# Sheet.net
KiCad netlist of a schematic drawn in Altium Designer
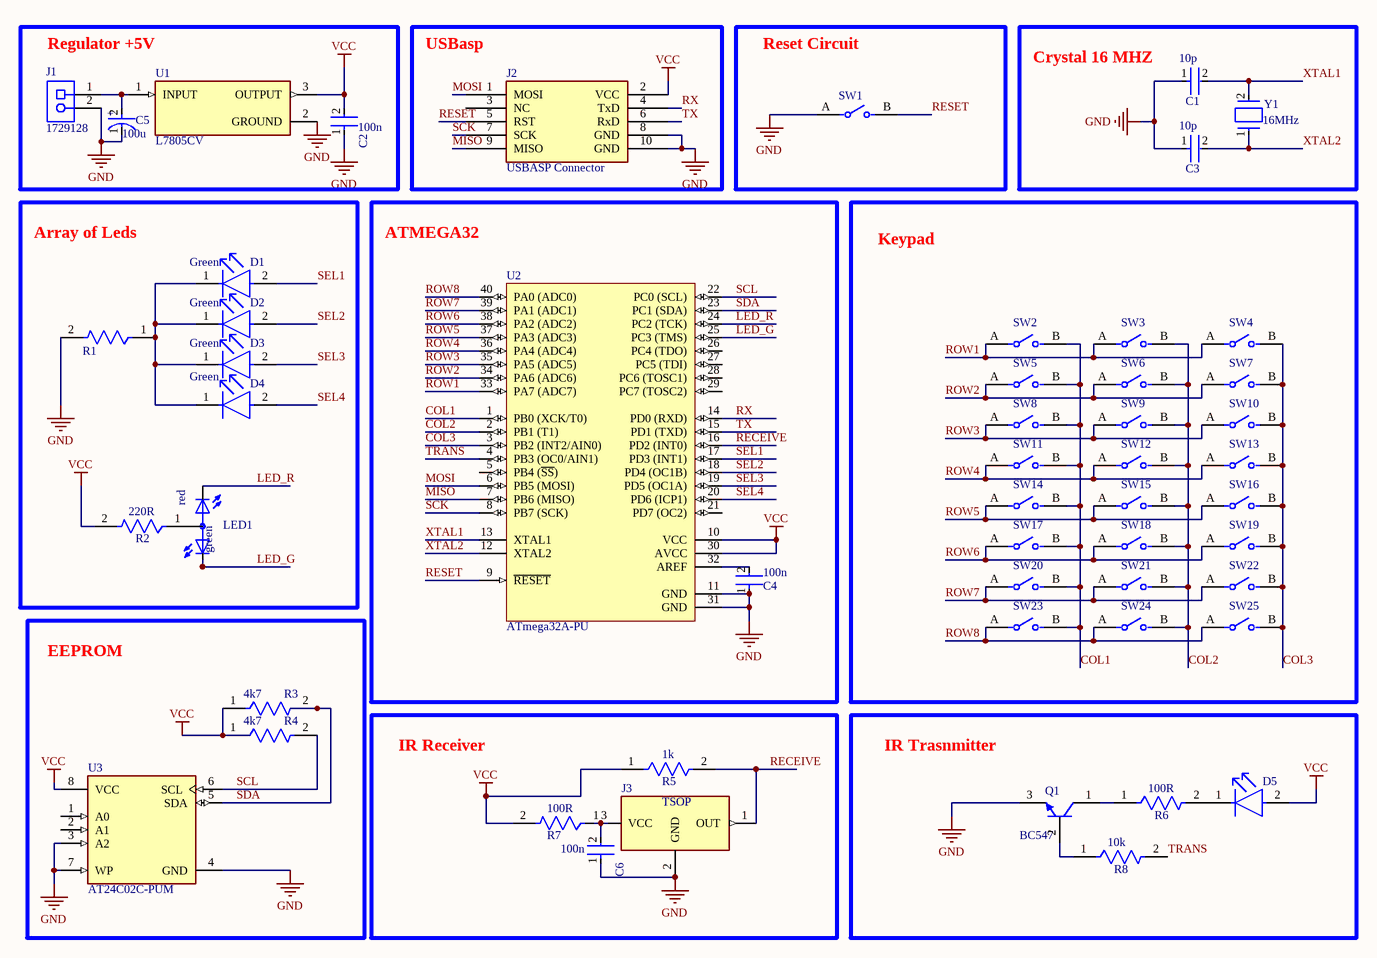
[diagram p0: Sheet.SchDoc]

(export (version "E")
  (design (tool "Eeschema 10.0.6"))
  (components
    (comp (ref "C1")
      (value "10p")
      (footprint "FP-K155L2-MFG")
      (description "K103K15X7RF5TL2 Multilayer Ceramic Capacitor, 0.01 uF, 50 V, ± 10%, X7R, Radial Leaded")
      (fields
        (field (name "VOLTAGE") "50V")
        (field (name "CAPACITANCE") "10p")
        (field (name "TOLERANCE") "10%")
      )
      (libsource (lib "Altium Content Vault") (part "02cd4be3c70576c341d710602a673aa"))
    )
    (comp (ref "C2")
      (value "K103K15X7RF5TL2")
      (footprint "FP-K155L2-MFG")
      (description "K103K15X7RF5TL2 Multilayer Ceramic Capacitor, 0.01 uF, 50 V, ± 10%, X7R, Radial Leaded")
      (fields
        (field (name "VOLTAGE") "50V")
        (field (name "CAPACITANCE") "100n")
        (field (name "TOLERANCE") "10%")
      )
      (libsource (lib "Altium Content Vault") (part "02cd4be3c70576c341d710602a673aa"))
    )
    (comp (ref "C3")
      (value "10p")
      (footprint "FP-K155L2-MFG")
      (description "K103K15X7RF5TL2 Multilayer Ceramic Capacitor, 0.01 uF, 50 V, ± 10%, X7R, Radial Leaded")
      (fields
        (field (name "VOLTAGE") "50V")
        (field (name "CAPACITANCE") "10p")
        (field (name "TOLERANCE") "10%")
      )
      (libsource (lib "Altium Content Vault") (part "02cd4be3c70576c341d710602a673aa"))
    )
    (comp (ref "C4")
      (value "100n")
      (footprint "FP-K155L2-MFG")
      (description "K103K15X7RF5TL2 Multilayer Ceramic Capacitor, 0.01 uF, 50 V, ± 10%, X7R, Radial Leaded")
      (fields (field (name "VOLTAGE") "50V") (field (name "TOLERANCE") "10%"))
      (libsource (lib "Altium Content Vault") (part "02cd4be3c70576c341d710602a673aa"))
    )
    (comp (ref "C5")
      (value "EEUHD1E101")
      (footprint "FP-RAD-TH-D_6_3_0_5-L_11-MFG")
      (description "Aluminum Electrolytic Capacitors (Radial Lead Type) AEC-Q200 Qualified 100uF ±20% 25V")
      (fields
        (field (name "TOLERANCE") "20%")
        (field (name "CAPACITANCE") "100u")
        (field (name "VOLTAGE") "25V")
      )
      (libsource (lib "Altium Content Vault") (part "a00bbbee19879c290e62620ae7e47b1"))
    )
    (comp (ref "C6")
      (value "K103K15X7RF5TL2")
      (footprint "FP-K155L2-MFG")
      (description "K103K15X7RF5TL2 Multilayer Ceramic Capacitor, 0.01 uF, 50 V, ± 10%, X7R, Radial Leaded")
      (fields
        (field (name "VOLTAGE") "50V")
        (field (name "CAPACITANCE") "100n")
        (field (name "TOLERANCE") "10%")
      )
      (libsource (lib "Altium Content Vault") (part "02cd4be3c70576c341d710602a673aa"))
    )
    (comp (ref "D1")
      (value "TLLG4401")
      (footprint "FP-6_544-5255_01-4-MFG")
      (description "TLLG4401 LED, Green, 2mcd, 3mmDia., T-1, +/-25deg, 565nm, 7mA, 1.9V Vf, 20V Vr, 20mW, -40")
      (fields (field (name "COLOR") "Green"))
      (libsource (lib "Altium Content Vault") (part "8706943c75ba83719d021d2fdc84c58"))
    )
    (comp (ref "D2")
      (value "TLLG4401")
      (footprint "FP-6_544-5255_01-4-MFG")
      (description "TLLG4401 LED, Green, 2mcd, 3mmDia., T-1, +/-25deg, 565nm, 7mA, 1.9V Vf, 20V Vr, 20mW, -40")
      (fields (field (name "COLOR") "Green"))
      (libsource (lib "Altium Content Vault") (part "8706943c75ba83719d021d2fdc84c58"))
    )
    (comp (ref "D3")
      (value "TLLG4401")
      (footprint "FP-6_544-5255_01-4-MFG")
      (description "TLLG4401 LED, Green, 2mcd, 3mmDia., T-1, +/-25deg, 565nm, 7mA, 1.9V Vf, 20V Vr, 20mW, -40")
      (fields (field (name "COLOR") "Green"))
      (libsource (lib "Altium Content Vault") (part "8706943c75ba83719d021d2fdc84c58"))
    )
    (comp (ref "D4")
      (value "TLLG4401")
      (footprint "FP-6_544-5255_01-4-MFG")
      (description "TLLG4401 LED, Green, 2mcd, 3mmDia., T-1, +/-25deg, 565nm, 7mA, 1.9V Vf, 20V Vr, 20mW, -40")
      (fields (field (name "COLOR") "Green"))
      (libsource (lib "Altium Content Vault") (part "8706943c75ba83719d021d2fdc84c58"))
    )
    (comp (ref "D5")
      (value "TLLG4401")
      (footprint "FP-6_544-5255_01-4-MFG")
      (description "TLLG4401 LED, Green, 2mcd, 3mmDia., T-1, +/-25deg, 565nm, 7mA, 1.9V Vf, 20V Vr, 20mW, -40")
      (libsource (lib "Altium Content Vault") (part "8706943c75ba83719d021d2fdc84c58"))
    )
    (comp (ref "J1")
      (value "1729128")
      (footprint "PHOE-1729128-2_V")
      (description "PCB Terminal Block, 13.5 A, 400 V, 2-Pin THD, RoHS, Bulk")
      (fields (field (name "MANUFACTURER") "Phoenix Contact"))
      (libsource (lib "Altium Content Vault") (part "CN-2P-F-R2"))
    )
    (comp (ref "J2")
      (value "USBASP Connector")
      (footprint "SamacSys:SHDR10W99P254_2X5_2032X889X927P")
      (description "Connector")
      (fields
        (field (name "MANUFACTURER_PART_NUMBER") "70246-1001")
        (field (name "MOUSER PART NUMBER") "538-70246-1001")
      )
      (libsource (lib "YoussifLIB") (part "USBASP Connector"))
    )
    (comp (ref "J3")
      (value "TSOP1838")
      (footprint "TSOP1838")
      (description "IR Remote Receiver 38KHz 35m 3-Pin")
      (fields (field (name "MF") "Vishay"))
      (libsource (lib "IR_Receiver") (part "TSOP1838"))
    )
    (comp (ref "LED1")
      (value "L-59EGW-CA")
      (footprint "L-59EGW-CA")
      (description "LED; 5mm; bicolour; red/green; 5mcd; 5mcd; 60Â°; Front: convex; anode")
      (fields (field (name "MF") "Kingbright"))
      (libsource (lib "YoussifLIB") (part "L-59EGW-CA"))
    )
    (comp (ref "Q1")
      (value "BC547")
      (footprint "ONSC-TO-92-3-29-11_AM_BL")
      (description "Amplifier Transistor, NPN Silicon, 3-Pin TO-92, Pb-Free, Ammo Box")
      (fields (field (name "MANUFACTURER") "On Semiconductor") (field (name "PARTNUMBER") "BC547BZL1G"))
      (libsource (lib "Altium Content Vault") (part "ONSC-NPN-C1B2E3-3"))
    )
    (comp (ref "R1")
      (value "MRS25000C1001FCT00")
      (footprint "FP-MRS25-MFG")
      (description "RES 1K OHM 0.6W 1% AXIAL")
      (fields (field (name "TOLERANCE") "1%"))
      (libsource (lib "Altium Content Vault") (part "1029c3af85768c4190bb7ad29bc67b5"))
    )
    (comp (ref "R2")
      (value "220R")
      (footprint "FP-MRS25-MFG")
      (description "RES 1K OHM 0.6W 1% AXIAL")
      (fields (field (name "TOLERANCE") "1%") (field (name "RESISTANCE") "220R"))
      (libsource (lib "Altium Content Vault") (part "1029c3af85768c4190bb7ad29bc67b5"))
    )
    (comp (ref "R3")
      (value "4k7")
      (footprint "FP-MRS25-MFG")
      (description "RES 1K OHM 0.6W 1% AXIAL")
      (fields (field (name "TOLERANCE") "1%") (field (name "RESISTANCE") "4k7"))
      (libsource (lib "Altium Content Vault") (part "1029c3af85768c4190bb7ad29bc67b5"))
    )
    (comp (ref "R4")
      (value "4k7")
      (footprint "FP-MRS25-MFG")
      (description "RES 1K OHM 0.6W 1% AXIAL")
      (fields (field (name "TOLERANCE") "1%") (field (name "RESISTANCE") "4k7"))
      (libsource (lib "Altium Content Vault") (part "1029c3af85768c4190bb7ad29bc67b5"))
    )
    (comp (ref "R5")
      (value "1k")
      (footprint "FP-MRS25-MFG")
      (description "RES 1K OHM 0.6W 1% AXIAL")
      (fields (field (name "TOLERANCE") "1%") (field (name "RESISTANCE") "1k"))
      (libsource (lib "Altium Content Vault") (part "1029c3af85768c4190bb7ad29bc67b5"))
    )
    (comp (ref "R6")
      (value "100R")
      (footprint "FP-MRS25-MFG")
      (description "RES 1K OHM 0.6W 1% AXIAL")
      (fields (field (name "TOLERANCE") "1%") (field (name "RESISTANCE") "100R"))
      (libsource (lib "Altium Content Vault") (part "1029c3af85768c4190bb7ad29bc67b5"))
    )
    (comp (ref "R7")
      (value "100R")
      (footprint "FP-MRS25-MFG")
      (description "RES 1K OHM 0.6W 1% AXIAL")
      (fields (field (name "TOLERANCE") "1%") (field (name "RESISTANCE") "100R"))
      (libsource (lib "Altium Content Vault") (part "1029c3af85768c4190bb7ad29bc67b5"))
    )
    (comp (ref "R8")
      (value "10k")
      (footprint "FP-MRS25-MFG")
      (description "RES 1K OHM 0.6W 1% AXIAL")
      (fields (field (name "TOLERANCE") "1%") (field (name "RESISTANCE") "10k"))
      (libsource (lib "Altium Content Vault") (part "1029c3af85768c4190bb7ad29bc67b5"))
    )
    (comp (ref "SW1")
      (value "EVQ-21505R")
      (footprint "FP-EVQ-21505R-MFG")
      (description "SWITCH TACTILE SPST-NO 0.02A 15V")
      (libsource (lib "Altium Content Vault") (part "2b0b2b19372efd94fa7681498149756"))
    )
    (comp (ref "SW2")
      (value "EVQ-21505R")
      (footprint "FP-EVQ-21505R-MFG")
      (description "SWITCH TACTILE SPST-NO 0.02A 15V")
      (libsource (lib "Altium Content Vault") (part "2b0b2b19372efd94fa7681498149756"))
    )
    (comp (ref "SW3")
      (value "EVQ-21505R")
      (footprint "FP-EVQ-21505R-MFG")
      (description "SWITCH TACTILE SPST-NO 0.02A 15V")
      (libsource (lib "Altium Content Vault") (part "2b0b2b19372efd94fa7681498149756"))
    )
    (comp (ref "SW4")
      (value "EVQ-21505R")
      (footprint "FP-EVQ-21505R-MFG")
      (description "SWITCH TACTILE SPST-NO 0.02A 15V")
      (libsource (lib "Altium Content Vault") (part "2b0b2b19372efd94fa7681498149756"))
    )
    (comp (ref "SW5")
      (value "EVQ-21505R")
      (footprint "FP-EVQ-21505R-MFG")
      (description "SWITCH TACTILE SPST-NO 0.02A 15V")
      (libsource (lib "Altium Content Vault") (part "2b0b2b19372efd94fa7681498149756"))
    )
    (comp (ref "SW6")
      (value "EVQ-21505R")
      (footprint "FP-EVQ-21505R-MFG")
      (description "SWITCH TACTILE SPST-NO 0.02A 15V")
      (libsource (lib "Altium Content Vault") (part "2b0b2b19372efd94fa7681498149756"))
    )
    (comp (ref "SW7")
      (value "EVQ-21505R")
      (footprint "FP-EVQ-21505R-MFG")
      (description "SWITCH TACTILE SPST-NO 0.02A 15V")
      (libsource (lib "Altium Content Vault") (part "2b0b2b19372efd94fa7681498149756"))
    )
    (comp (ref "SW8")
      (value "EVQ-21505R")
      (footprint "FP-EVQ-21505R-MFG")
      (description "SWITCH TACTILE SPST-NO 0.02A 15V")
      (libsource (lib "Altium Content Vault") (part "2b0b2b19372efd94fa7681498149756"))
    )
    (comp (ref "SW9")
      (value "EVQ-21505R")
      (footprint "FP-EVQ-21505R-MFG")
      (description "SWITCH TACTILE SPST-NO 0.02A 15V")
      (libsource (lib "Altium Content Vault") (part "2b0b2b19372efd94fa7681498149756"))
    )
    (comp (ref "SW10")
      (value "EVQ-21505R")
      (footprint "FP-EVQ-21505R-MFG")
      (description "SWITCH TACTILE SPST-NO 0.02A 15V")
      (libsource (lib "Altium Content Vault") (part "2b0b2b19372efd94fa7681498149756"))
    )
    (comp (ref "SW11")
      (value "EVQ-21505R")
      (footprint "FP-EVQ-21505R-MFG")
      (description "SWITCH TACTILE SPST-NO 0.02A 15V")
      (libsource (lib "Altium Content Vault") (part "2b0b2b19372efd94fa7681498149756"))
    )
    (comp (ref "SW12")
      (value "EVQ-21505R")
      (footprint "FP-EVQ-21505R-MFG")
      (description "SWITCH TACTILE SPST-NO 0.02A 15V")
      (libsource (lib "Altium Content Vault") (part "2b0b2b19372efd94fa7681498149756"))
    )
    (comp (ref "SW13")
      (value "EVQ-21505R")
      (footprint "FP-EVQ-21505R-MFG")
      (description "SWITCH TACTILE SPST-NO 0.02A 15V")
      (libsource (lib "Altium Content Vault") (part "2b0b2b19372efd94fa7681498149756"))
    )
    (comp (ref "SW14")
      (value "EVQ-21505R")
      (footprint "FP-EVQ-21505R-MFG")
      (description "SWITCH TACTILE SPST-NO 0.02A 15V")
      (libsource (lib "Altium Content Vault") (part "2b0b2b19372efd94fa7681498149756"))
    )
    (comp (ref "SW15")
      (value "EVQ-21505R")
      (footprint "FP-EVQ-21505R-MFG")
      (description "SWITCH TACTILE SPST-NO 0.02A 15V")
      (libsource (lib "Altium Content Vault") (part "2b0b2b19372efd94fa7681498149756"))
    )
    (comp (ref "SW16")
      (value "EVQ-21505R")
      (footprint "FP-EVQ-21505R-MFG")
      (description "SWITCH TACTILE SPST-NO 0.02A 15V")
      (libsource (lib "Altium Content Vault") (part "2b0b2b19372efd94fa7681498149756"))
    )
    (comp (ref "SW17")
      (value "EVQ-21505R")
      (footprint "FP-EVQ-21505R-MFG")
      (description "SWITCH TACTILE SPST-NO 0.02A 15V")
      (libsource (lib "Altium Content Vault") (part "2b0b2b19372efd94fa7681498149756"))
    )
    (comp (ref "SW18")
      (value "EVQ-21505R")
      (footprint "FP-EVQ-21505R-MFG")
      (description "SWITCH TACTILE SPST-NO 0.02A 15V")
      (libsource (lib "Altium Content Vault") (part "2b0b2b19372efd94fa7681498149756"))
    )
    (comp (ref "SW19")
      (value "EVQ-21505R")
      (footprint "FP-EVQ-21505R-MFG")
      (description "SWITCH TACTILE SPST-NO 0.02A 15V")
      (libsource (lib "Altium Content Vault") (part "2b0b2b19372efd94fa7681498149756"))
    )
    (comp (ref "SW20")
      (value "EVQ-21505R")
      (footprint "FP-EVQ-21505R-MFG")
      (description "SWITCH TACTILE SPST-NO 0.02A 15V")
      (libsource (lib "Altium Content Vault") (part "2b0b2b19372efd94fa7681498149756"))
    )
    (comp (ref "SW21")
      (value "EVQ-21505R")
      (footprint "FP-EVQ-21505R-MFG")
      (description "SWITCH TACTILE SPST-NO 0.02A 15V")
      (libsource (lib "Altium Content Vault") (part "2b0b2b19372efd94fa7681498149756"))
    )
    (comp (ref "SW22")
      (value "EVQ-21505R")
      (footprint "FP-EVQ-21505R-MFG")
      (description "SWITCH TACTILE SPST-NO 0.02A 15V")
      (libsource (lib "Altium Content Vault") (part "2b0b2b19372efd94fa7681498149756"))
    )
    (comp (ref "SW23")
      (value "EVQ-21505R")
      (footprint "FP-EVQ-21505R-MFG")
      (description "SWITCH TACTILE SPST-NO 0.02A 15V")
      (libsource (lib "Altium Content Vault") (part "2b0b2b19372efd94fa7681498149756"))
    )
    (comp (ref "SW24")
      (value "EVQ-21505R")
      (footprint "FP-EVQ-21505R-MFG")
      (description "SWITCH TACTILE SPST-NO 0.02A 15V")
      (libsource (lib "Altium Content Vault") (part "2b0b2b19372efd94fa7681498149756"))
    )
    (comp (ref "SW25")
      (value "EVQ-21505R")
      (footprint "FP-EVQ-21505R-MFG")
      (description "SWITCH TACTILE SPST-NO 0.02A 15V")
      (libsource (lib "Altium Content Vault") (part "2b0b2b19372efd94fa7681498149756"))
    )
    (comp (ref "U1")
      (value "L7805CV")
      (footprint "TO255P1040X460X1968-3")
      (description "Linear Voltage Regulator IC Positive Fixed 1 Output 1.5A TO-220")
      (fields (field (name "MF") "STMicroelectronics"))
      (libsource (lib "L7805CV") (part "L7805CV"))
    )
    (comp (ref "U2")
      (value "ATmega32A-PU")
      (footprint "40P6")
      (libsource (lib "Altium Content Vault") (part "MC-8B-AT16A-IL40"))
    )
    (comp (ref "U3")
      (value "AT24C02C-PUM")
      (footprint "FP-C04-018-P-MFG")
      (description "AT24C02C-PUM EEPROM Serial-2Wire 2K-bit 256 x 8 1.8V/2.5V/3.3V/5V 8-Pin PDIP W Bulk - Rail/Tube")
      (libsource (lib "Altium Content Vault") (part "089d7b6fce1835f83e6218732eee8eb"))
    )
    (comp (ref "Y1")
      (value "16MHz")
      (footprint "FP-ECS-80-20-4X-MFG")
      (fields (field (name "FREQUENCY") "16MHz") (field (name "TOLERANCE") "0.003%"))
      (libsource (lib "Altium Content Vault") (part "c23a69dc6c9e2f18f2079038eb95dd1"))
    )
  )
  (nets
    (net (code "1") (name "/COL1") (class "Default")
      (node (ref "SW11") (pin "B") (pinfunction "B_B") (pintype "passive"))
      (node (ref "SW14") (pin "B") (pinfunction "B_B") (pintype "passive"))
      (node (ref "SW17") (pin "B") (pinfunction "B_B") (pintype "passive"))
      (node (ref "SW2") (pin "B") (pinfunction "B_B") (pintype "passive"))
      (node (ref "SW20") (pin "B") (pinfunction "B_B") (pintype "passive"))
      (node (ref "SW23") (pin "B") (pinfunction "B_B") (pintype "passive"))
      (node (ref "SW5") (pin "B") (pinfunction "B_B") (pintype "passive"))
      (node (ref "SW8") (pin "B") (pinfunction "B_B") (pintype "passive"))
      (node (ref "U2") (pin "1") (pinfunction "PB0_(XCK/T0)_1") (pintype "bidirectional"))
    )
    (net (code "2") (name "/COL2") (class "Default")
      (node (ref "SW12") (pin "B") (pinfunction "B_B") (pintype "passive"))
      (node (ref "SW15") (pin "B") (pinfunction "B_B") (pintype "passive"))
      (node (ref "SW18") (pin "B") (pinfunction "B_B") (pintype "passive"))
      (node (ref "SW21") (pin "B") (pinfunction "B_B") (pintype "passive"))
      (node (ref "SW24") (pin "B") (pinfunction "B_B") (pintype "passive"))
      (node (ref "SW3") (pin "B") (pinfunction "B_B") (pintype "passive"))
      (node (ref "SW6") (pin "B") (pinfunction "B_B") (pintype "passive"))
      (node (ref "SW9") (pin "B") (pinfunction "B_B") (pintype "passive"))
      (node (ref "U2") (pin "2") (pinfunction "PB1_(T1)_2") (pintype "bidirectional"))
    )
    (net (code "3") (name "/COL3") (class "Default")
      (node (ref "SW10") (pin "B") (pinfunction "B_B") (pintype "passive"))
      (node (ref "SW13") (pin "B") (pinfunction "B_B") (pintype "passive"))
      (node (ref "SW16") (pin "B") (pinfunction "B_B") (pintype "passive"))
      (node (ref "SW19") (pin "B") (pinfunction "B_B") (pintype "passive"))
      (node (ref "SW22") (pin "B") (pinfunction "B_B") (pintype "passive"))
      (node (ref "SW25") (pin "B") (pinfunction "B_B") (pintype "passive"))
      (node (ref "SW4") (pin "B") (pinfunction "B_B") (pintype "passive"))
      (node (ref "SW7") (pin "B") (pinfunction "B_B") (pintype "passive"))
      (node (ref "U2") (pin "3") (pinfunction "PB2_(INT2/AIN0)_3") (pintype "bidirectional"))
    )
    (net (code "4") (name "/LED_G") (class "Default")
      (node (ref "LED1") (pin "3") (pinfunction "CG_3") (pintype "passive"))
      (node (ref "U2") (pin "25") (pinfunction "PC3_(TMS)_25") (pintype "bidirectional"))
    )
    (net (code "5") (name "/LED_R") (class "Default")
      (node (ref "LED1") (pin "1") (pinfunction "CR_1") (pintype "passive"))
      (node (ref "U2") (pin "24") (pinfunction "PC2_(TCK)_24") (pintype "bidirectional"))
    )
    (net (code "6") (name "/MISO") (class "Default")
      (node (ref "J2") (pin "9") (pinfunction "MISO_9") (pintype "passive"))
      (node (ref "U2") (pin "7") (pinfunction "PB6_(MISO)_7") (pintype "bidirectional"))
    )
    (net (code "7") (name "/MOSI") (class "Default")
      (node (ref "J2") (pin "1") (pinfunction "MOSI_1") (pintype "passive"))
      (node (ref "U2") (pin "6") (pinfunction "PB5_(MOSI)_6") (pintype "bidirectional"))
    )
    (net (code "8") (name "/RECEIVE") (class "Default")
      (node (ref "J3") (pin "1") (pinfunction "OUT_1") (pintype "output"))
      (node (ref "R5") (pin "2") (pinfunction "2_2") (pintype "passive"))
      (node (ref "U2") (pin "16") (pinfunction "PD2_(INT0)_16") (pintype "bidirectional"))
    )
    (net (code "9") (name "/RESET") (class "Default")
      (node (ref "J2") (pin "5") (pinfunction "RST_5") (pintype "passive"))
      (node (ref "SW1") (pin "B") (pinfunction "B_B") (pintype "passive"))
      (node (ref "U2") (pin "9") (pinfunction "~{RESET}_9") (pintype "input"))
    )
    (net (code "10") (name "/ROW1") (class "Default")
      (node (ref "SW2") (pin "A") (pinfunction "A_A") (pintype "passive"))
      (node (ref "SW3") (pin "A") (pinfunction "A_A") (pintype "passive"))
      (node (ref "SW4") (pin "A") (pinfunction "A_A") (pintype "passive"))
      (node (ref "U2") (pin "33") (pinfunction "PA7_(ADC7)_33") (pintype "bidirectional"))
    )
    (net (code "11") (name "/ROW2") (class "Default")
      (node (ref "SW5") (pin "A") (pinfunction "A_A") (pintype "passive"))
      (node (ref "SW6") (pin "A") (pinfunction "A_A") (pintype "passive"))
      (node (ref "SW7") (pin "A") (pinfunction "A_A") (pintype "passive"))
      (node (ref "U2") (pin "34") (pinfunction "PA6_(ADC6)_34") (pintype "bidirectional"))
    )
    (net (code "12") (name "/ROW3") (class "Default")
      (node (ref "SW10") (pin "A") (pinfunction "A_A") (pintype "passive"))
      (node (ref "SW8") (pin "A") (pinfunction "A_A") (pintype "passive"))
      (node (ref "SW9") (pin "A") (pinfunction "A_A") (pintype "passive"))
      (node (ref "U2") (pin "35") (pinfunction "PA5_(ADC5)_35") (pintype "bidirectional"))
    )
    (net (code "13") (name "/ROW4") (class "Default")
      (node (ref "SW11") (pin "A") (pinfunction "A_A") (pintype "passive"))
      (node (ref "SW12") (pin "A") (pinfunction "A_A") (pintype "passive"))
      (node (ref "SW13") (pin "A") (pinfunction "A_A") (pintype "passive"))
      (node (ref "U2") (pin "36") (pinfunction "PA4_(ADC4)_36") (pintype "bidirectional"))
    )
    (net (code "14") (name "/ROW5") (class "Default")
      (node (ref "SW14") (pin "A") (pinfunction "A_A") (pintype "passive"))
      (node (ref "SW15") (pin "A") (pinfunction "A_A") (pintype "passive"))
      (node (ref "SW16") (pin "A") (pinfunction "A_A") (pintype "passive"))
      (node (ref "U2") (pin "37") (pinfunction "PA3_(ADC3)_37") (pintype "bidirectional"))
    )
    (net (code "15") (name "/ROW6") (class "Default")
      (node (ref "SW17") (pin "A") (pinfunction "A_A") (pintype "passive"))
      (node (ref "SW18") (pin "A") (pinfunction "A_A") (pintype "passive"))
      (node (ref "SW19") (pin "A") (pinfunction "A_A") (pintype "passive"))
      (node (ref "U2") (pin "38") (pinfunction "PA2_(ADC2)_38") (pintype "bidirectional"))
    )
    (net (code "16") (name "/ROW7") (class "Default")
      (node (ref "SW20") (pin "A") (pinfunction "A_A") (pintype "passive"))
      (node (ref "SW21") (pin "A") (pinfunction "A_A") (pintype "passive"))
      (node (ref "SW22") (pin "A") (pinfunction "A_A") (pintype "passive"))
      (node (ref "U2") (pin "39") (pinfunction "PA1_(ADC1)_39") (pintype "bidirectional"))
    )
    (net (code "17") (name "/ROW8") (class "Default")
      (node (ref "SW23") (pin "A") (pinfunction "A_A") (pintype "passive"))
      (node (ref "SW24") (pin "A") (pinfunction "A_A") (pintype "passive"))
      (node (ref "SW25") (pin "A") (pinfunction "A_A") (pintype "passive"))
      (node (ref "U2") (pin "40") (pinfunction "PA0_(ADC0)_40") (pintype "bidirectional"))
    )
    (net (code "18") (name "/RX") (class "Default")
      (node (ref "J2") (pin "4") (pinfunction "TxD_4") (pintype "passive"))
      (node (ref "U2") (pin "14") (pinfunction "PD0_(RXD)_14") (pintype "bidirectional"))
    )
    (net (code "19") (name "/SCK") (class "Default")
      (node (ref "J2") (pin "7") (pinfunction "SCK_7") (pintype "passive"))
      (node (ref "U2") (pin "8") (pinfunction "PB7_(SCK)_8") (pintype "bidirectional"))
    )
    (net (code "20") (name "/SCL") (class "Default")
      (node (ref "R4") (pin "2") (pinfunction "2_2") (pintype "passive"))
      (node (ref "U2") (pin "22") (pinfunction "PC0_(SCL)_22") (pintype "bidirectional"))
      (node (ref "U3") (pin "6") (pinfunction "SCL_6") (pintype "input"))
    )
    (net (code "21") (name "/SDA") (class "Default")
      (node (ref "R3") (pin "2") (pinfunction "2_2") (pintype "passive"))
      (node (ref "U2") (pin "23") (pinfunction "PC1_(SDA)_23") (pintype "bidirectional"))
      (node (ref "U3") (pin "5") (pinfunction "SDA_5") (pintype "bidirectional"))
    )
    (net (code "22") (name "/SEL1") (class "Default")
      (node (ref "D1") (pin "2") (pinfunction "A_2") (pintype "passive"))
      (node (ref "U2") (pin "17") (pinfunction "PD3_(INT1)_17") (pintype "bidirectional"))
    )
    (net (code "23") (name "/SEL2") (class "Default")
      (node (ref "D2") (pin "2") (pinfunction "A_2") (pintype "passive"))
      (node (ref "U2") (pin "18") (pinfunction "PD4_(OC1B)_18") (pintype "bidirectional"))
    )
    (net (code "24") (name "/SEL3") (class "Default")
      (node (ref "D3") (pin "2") (pinfunction "A_2") (pintype "passive"))
      (node (ref "U2") (pin "19") (pinfunction "PD5_(OC1A)_19") (pintype "bidirectional"))
    )
    (net (code "25") (name "/SEL4") (class "Default")
      (node (ref "D4") (pin "2") (pinfunction "A_2") (pintype "passive"))
      (node (ref "U2") (pin "20") (pinfunction "PD6_(ICP1)_20") (pintype "bidirectional"))
    )
    (net (code "26") (name "/TRANS") (class "Default")
      (node (ref "R8") (pin "2") (pinfunction "2_2") (pintype "passive"))
      (node (ref "U2") (pin "4") (pinfunction "PB3_(OC0/AIN1)_4") (pintype "bidirectional"))
    )
    (net (code "27") (name "/TX") (class "Default")
      (node (ref "J2") (pin "6") (pinfunction "RxD_6") (pintype "passive"))
      (node (ref "U2") (pin "15") (pinfunction "PD1_(TXD)_15") (pintype "bidirectional"))
    )
    (net (code "28") (name "/XTAL1") (class "Default")
      (node (ref "C1") (pin "2") (pinfunction "2_2") (pintype "passive"))
      (node (ref "U2") (pin "13") (pinfunction "XTAL1_13") (pintype "passive"))
      (node (ref "Y1") (pin "2") (pinfunction "2_2") (pintype "passive"))
    )
    (net (code "29") (name "/XTAL2") (class "Default")
      (node (ref "C3") (pin "2") (pinfunction "2_2") (pintype "passive"))
      (node (ref "U2") (pin "12") (pinfunction "XTAL2_12") (pintype "passive"))
      (node (ref "Y1") (pin "1") (pinfunction "1_1") (pintype "passive"))
    )
    (net (code "30") (name "GND") (class "Default")
      (node (ref "C1") (pin "1") (pinfunction "1_1") (pintype "passive"))
      (node (ref "C2") (pin "1") (pinfunction "1_1") (pintype "passive"))
      (node (ref "C3") (pin "1") (pinfunction "1_1") (pintype "passive"))
      (node (ref "C4") (pin "1") (pinfunction "1_1") (pintype "passive"))
      (node (ref "C5") (pin "1") (pinfunction "C_1") (pintype "passive"))
      (node (ref "C6") (pin "1") (pinfunction "1_1") (pintype "passive"))
      (node (ref "J1") (pin "2") (pinfunction "2_2") (pintype "passive"))
      (node (ref "J2") (pin "10") (pinfunction "GND_10") (pintype "passive"))
      (node (ref "J2") (pin "8") (pinfunction "GND_8") (pintype "passive"))
      (node (ref "J3") (pin "2") (pinfunction "GND_2") (pintype "power_in"))
      (node (ref "Q1") (pin "3") (pinfunction "E_3") (pintype "passive"))
      (node (ref "R1") (pin "2") (pinfunction "2_2") (pintype "passive"))
      (node (ref "SW1") (pin "A") (pinfunction "A_A") (pintype "passive"))
      (node (ref "U1") (pin "2") (pinfunction "GROUND_2") (pintype "power_in"))
      (node (ref "U2") (pin "11") (pinfunction "GND_11") (pintype "power_in"))
      (node (ref "U2") (pin "31") (pinfunction "GND_31") (pintype "power_in"))
      (node (ref "U3") (pin "3") (pinfunction "A2_3") (pintype "input"))
      (node (ref "U3") (pin "4") (pinfunction "GND_4") (pintype "power_in"))
      (node (ref "U3") (pin "7") (pinfunction "WP_7") (pintype "input"))
    )
    (net (code "31") (name "Net-(C5-A)") (class "Default")
      (node (ref "C5") (pin "2") (pinfunction "A_2") (pintype "passive"))
      (node (ref "J1") (pin "1") (pinfunction "1_1") (pintype "passive"))
      (node (ref "U1") (pin "1") (pinfunction "INPUT_1") (pintype "input"))
    )
    (net (code "32") (name "Net-(D1-C)") (class "Default")
      (node (ref "D1") (pin "1") (pinfunction "C_1") (pintype "passive"))
      (node (ref "D2") (pin "1") (pinfunction "C_1") (pintype "passive"))
      (node (ref "D3") (pin "1") (pinfunction "C_1") (pintype "passive"))
      (node (ref "D4") (pin "1") (pinfunction "C_1") (pintype "passive"))
      (node (ref "R1") (pin "1") (pinfunction "1_1") (pintype "passive"))
    )
    (net (code "33") (name "Net-(D5-C)") (class "Default")
      (node (ref "D5") (pin "1") (pinfunction "C_1") (pintype "passive"))
      (node (ref "R6") (pin "2") (pinfunction "2_2") (pintype "passive"))
    )
    (net (code "34") (name "Net-(J3-VCC)") (class "Default")
      (node (ref "C6") (pin "2") (pinfunction "2_2") (pintype "passive"))
      (node (ref "J3") (pin "3") (pinfunction "VCC_3") (pintype "power_in"))
      (node (ref "R7") (pin "1") (pinfunction "1_1") (pintype "passive"))
    )
    (net (code "35") (name "Net-(LED1-A)") (class "Default")
      (node (ref "LED1") (pin "2") (pinfunction "A_2") (pintype "passive"))
      (node (ref "R2") (pin "1") (pinfunction "1_1") (pintype "passive"))
    )
    (net (code "36") (name "Net-(Q1-B)") (class "Default")
      (node (ref "Q1") (pin "2") (pinfunction "B_2") (pintype "passive"))
      (node (ref "R8") (pin "1") (pinfunction "1_1") (pintype "passive"))
    )
    (net (code "37") (name "Net-(Q1-C)") (class "Default")
      (node (ref "Q1") (pin "1") (pinfunction "C_1") (pintype "passive"))
      (node (ref "R6") (pin "1") (pinfunction "1_1") (pintype "passive"))
    )
    (net (code "38") (name "Net-(U2-AREF)") (class "Default")
      (node (ref "C4") (pin "2") (pinfunction "2_2") (pintype "passive"))
      (node (ref "U2") (pin "32") (pinfunction "AREF_32") (pintype "power_in"))
    )
    (net (code "39") (name "VCC") (class "Default")
      (node (ref "C2") (pin "2") (pinfunction "2_2") (pintype "passive"))
      (node (ref "D5") (pin "2") (pinfunction "A_2") (pintype "passive"))
      (node (ref "J2") (pin "2") (pinfunction "VCC_2") (pintype "passive"))
      (node (ref "R2") (pin "2") (pinfunction "2_2") (pintype "passive"))
      (node (ref "R3") (pin "1") (pinfunction "1_1") (pintype "passive"))
      (node (ref "R4") (pin "1") (pinfunction "1_1") (pintype "passive"))
      (node (ref "R5") (pin "1") (pinfunction "1_1") (pintype "passive"))
      (node (ref "R7") (pin "2") (pinfunction "2_2") (pintype "passive"))
      (node (ref "U1") (pin "3") (pinfunction "OUTPUT_3") (pintype "output"))
      (node (ref "U2") (pin "10") (pinfunction "VCC_10") (pintype "power_in"))
      (node (ref "U2") (pin "30") (pinfunction "AVCC_30") (pintype "power_in"))
      (node (ref "U3") (pin "8") (pinfunction "VCC_8") (pintype "power_in"))
    )
    (net (code "40") (name "unconnected-(J2-NC-Pad3)") (class "Default")
      (node (ref "J2") (pin "3") (pinfunction "NC_3") (pintype "passive"))
    )
    (net (code "41") (name "unconnected-(U2-PB4_(~{SS})-Pad5)") (class "Default")
      (node (ref "U2") (pin "5") (pinfunction "PB4_(~{SS})_5") (pintype "bidirectional"))
    )
    (net (code "42") (name "unconnected-(U2-PC4_(TDO)-Pad26)") (class "Default")
      (node (ref "U2") (pin "26") (pinfunction "PC4_(TDO)_26") (pintype "bidirectional"))
    )
    (net (code "43") (name "unconnected-(U2-PC5_(TDI)-Pad27)") (class "Default")
      (node (ref "U2") (pin "27") (pinfunction "PC5_(TDI)_27") (pintype "bidirectional"))
    )
    (net (code "44") (name "unconnected-(U2-PC6_(TOSC1)-Pad28)") (class "Default")
      (node (ref "U2") (pin "28") (pinfunction "PC6_(TOSC1)_28") (pintype "bidirectional"))
    )
    (net (code "45") (name "unconnected-(U2-PC7_(TOSC2)-Pad29)") (class "Default")
      (node (ref "U2") (pin "29") (pinfunction "PC7_(TOSC2)_29") (pintype "bidirectional"))
    )
    (net (code "46") (name "unconnected-(U2-PD7_(OC2)-Pad21)") (class "Default")
      (node (ref "U2") (pin "21") (pinfunction "PD7_(OC2)_21") (pintype "bidirectional"))
    )
    (net (code "47") (name "unconnected-(U3-A0-Pad1)") (class "Default")
      (node (ref "U3") (pin "1") (pinfunction "A0_1") (pintype "input"))
    )
    (net (code "48") (name "unconnected-(U3-A1-Pad2)") (class "Default")
      (node (ref "U3") (pin "2") (pinfunction "A1_2") (pintype "input"))
    )
  )
)
